# suit.net
KiCad netlist of a schematic drawn in EAGLE
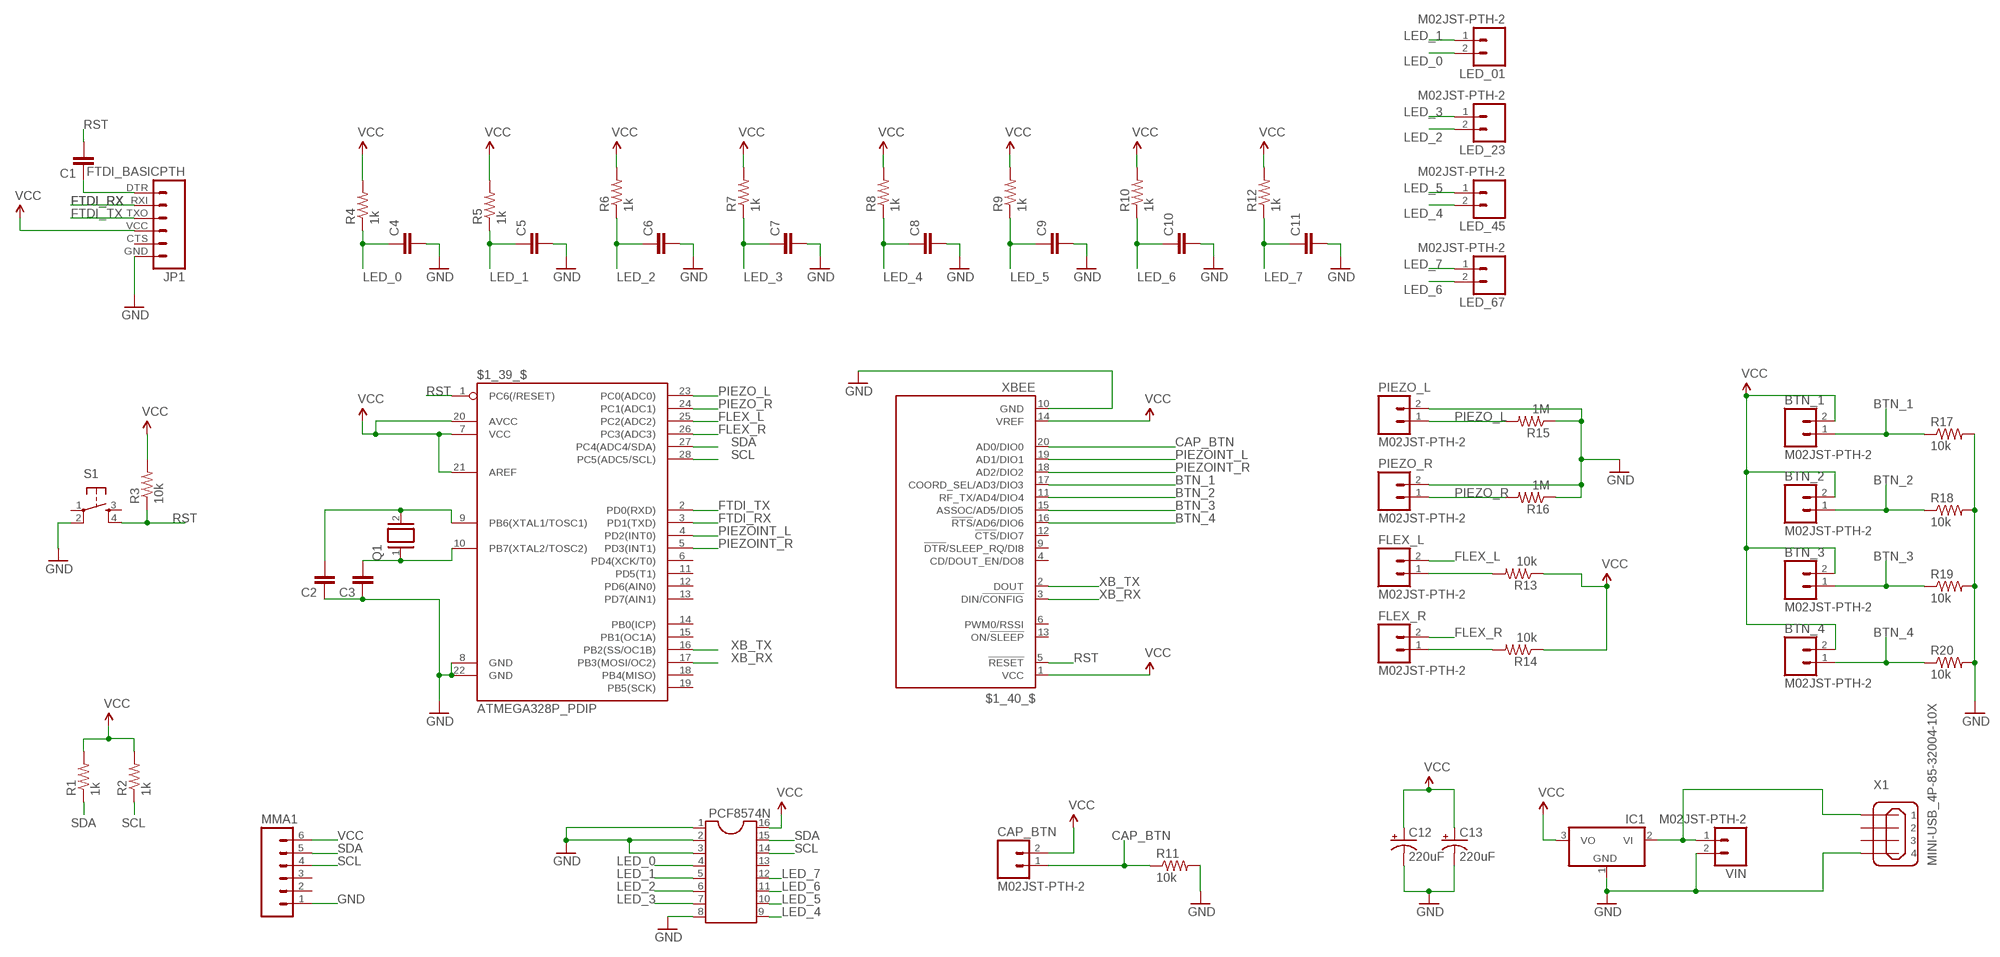
[diagram p0: schematic, sheet 1]

(export (version "E")
  (design (tool "Eeschema 10.0.6"))
  (components
    (comp (ref "$1_39_$")
      (value "ATMEGA328P_PDIP")
      (footprint "eagle-import:DIL28-3")
      (libsource (lib "eagle-import") (part "ATMEGA328P_PDIP"))
    )
    (comp (ref "$1_40_$")
      (value "XBEE")
      (footprint "eagle-import:XBEE")
      (fields (field (name "MPN") "XBP24-Z7UIT-004"))
      (libsource (lib "eagle-import") (part "XBEE"))
    )
    (comp (ref "BTN_1")
      (value "M02JST-PTH-2")
      (footprint "eagle-import:JST-2-PTH")
      (libsource (lib "eagle-import") (part "M02JST-PTH-2"))
    )
    (comp (ref "BTN_2")
      (value "M02JST-PTH-2")
      (footprint "eagle-import:JST-2-PTH")
      (libsource (lib "eagle-import") (part "M02JST-PTH-2"))
    )
    (comp (ref "BTN_3")
      (value "M02JST-PTH-2")
      (footprint "eagle-import:JST-2-PTH")
      (libsource (lib "eagle-import") (part "M02JST-PTH-2"))
    )
    (comp (ref "BTN_4")
      (value "M02JST-PTH-2")
      (footprint "eagle-import:JST-2-PTH")
      (libsource (lib "eagle-import") (part "M02JST-PTH-2"))
    )
    (comp (ref "C1")
      (value "CAPEZ")
      (footprint "eagle-import:CAP-PTH-SMALLEZ")
      (libsource (lib "eagle-import") (part "CAPEZ"))
    )
    (comp (ref "C2")
      (value "CAPEZ")
      (footprint "eagle-import:CAP-PTH-SMALLEZ")
      (libsource (lib "eagle-import") (part "CAPEZ"))
    )
    (comp (ref "C3")
      (value "CAPEZ")
      (footprint "eagle-import:CAP-PTH-SMALLEZ")
      (libsource (lib "eagle-import") (part "CAPEZ"))
    )
    (comp (ref "C4")
      (value "CAPEZ")
      (footprint "eagle-import:CAP-PTH-SMALLEZ")
      (libsource (lib "eagle-import") (part "CAPEZ"))
    )
    (comp (ref "C5")
      (value "CAPEZ")
      (footprint "eagle-import:CAP-PTH-SMALLEZ")
      (libsource (lib "eagle-import") (part "CAPEZ"))
    )
    (comp (ref "C6")
      (value "CAPEZ")
      (footprint "eagle-import:CAP-PTH-SMALLEZ")
      (libsource (lib "eagle-import") (part "CAPEZ"))
    )
    (comp (ref "C7")
      (value "CAPEZ")
      (footprint "eagle-import:CAP-PTH-SMALLEZ")
      (libsource (lib "eagle-import") (part "CAPEZ"))
    )
    (comp (ref "C8")
      (value "CAPEZ")
      (footprint "eagle-import:CAP-PTH-SMALLEZ")
      (libsource (lib "eagle-import") (part "CAPEZ"))
    )
    (comp (ref "C9")
      (value "CAPEZ")
      (footprint "eagle-import:CAP-PTH-SMALLEZ")
      (libsource (lib "eagle-import") (part "CAPEZ"))
    )
    (comp (ref "C10")
      (value "CAPEZ")
      (footprint "eagle-import:CAP-PTH-SMALLEZ")
      (libsource (lib "eagle-import") (part "CAPEZ"))
    )
    (comp (ref "C11")
      (value "CAPEZ")
      (footprint "eagle-import:CAP-PTH-SMALLEZ")
      (libsource (lib "eagle-import") (part "CAPEZ"))
    )
    (comp (ref "C12")
      (value "220uF")
      (footprint "eagle-import:B45181A")
      (libsource (lib "eagle-import") (part "CPOL-USB45181A"))
    )
    (comp (ref "C13")
      (value "220uF")
      (footprint "eagle-import:B45181A")
      (libsource (lib "eagle-import") (part "CPOL-USB45181A"))
    )
    (comp (ref "CAP_BTN")
      (value "M02JST-PTH-2")
      (footprint "eagle-import:JST-2-PTH")
      (libsource (lib "eagle-import") (part "M02JST-PTH-2"))
    )
    (comp (ref "FLEX_L")
      (value "M02JST-PTH-2")
      (footprint "eagle-import:JST-2-PTH")
      (libsource (lib "eagle-import") (part "M02JST-PTH-2"))
    )
    (comp (ref "FLEX_R")
      (value "M02JST-PTH-2")
      (footprint "eagle-import:JST-2-PTH")
      (libsource (lib "eagle-import") (part "M02JST-PTH-2"))
    )
    (comp (ref "IC1")
      (value "79L05Z")
      (footprint "eagle-import:TO92")
      (libsource (lib "eagle-import") (part "79ZL05"))
    )
    (comp (ref "JP1")
      (value "FTDI_BASICPTH")
      (footprint "eagle-import:FTDI_BASIC")
      (libsource (lib "eagle-import") (part "FTDI_BASICPTH"))
    )
    (comp (ref "LED_01")
      (value "M02JST-PTH-2")
      (footprint "eagle-import:JST-2-PTH")
      (libsource (lib "eagle-import") (part "M02JST-PTH-2"))
    )
    (comp (ref "LED_23")
      (value "M02JST-PTH-2")
      (footprint "eagle-import:JST-2-PTH")
      (libsource (lib "eagle-import") (part "M02JST-PTH-2"))
    )
    (comp (ref "LED_45")
      (value "M02JST-PTH-2")
      (footprint "eagle-import:JST-2-PTH")
      (libsource (lib "eagle-import") (part "M02JST-PTH-2"))
    )
    (comp (ref "LED_67")
      (value "M02JST-PTH-2")
      (footprint "eagle-import:JST-2-PTH")
      (libsource (lib "eagle-import") (part "M02JST-PTH-2"))
    )
    (comp (ref "MMA1")
      (value "M06FEMALE_LOCK")
      (footprint "eagle-import:1X06_FEMALE_LOCK.010")
      (libsource (lib "eagle-import") (part "M06FEMALE_LOCK"))
    )
    (comp (ref "PCF8574N")
      (value "DIL16S")
      (footprint "eagle-import:SOCKET-16")
      (libsource (lib "eagle-import") (part "DIL16S"))
    )
    (comp (ref "PIEZO_L")
      (value "M02JST-PTH-2")
      (footprint "eagle-import:JST-2-PTH")
      (libsource (lib "eagle-import") (part "M02JST-PTH-2"))
    )
    (comp (ref "PIEZO_R")
      (value "M02JST-PTH-2")
      (footprint "eagle-import:JST-2-PTH")
      (libsource (lib "eagle-import") (part "M02JST-PTH-2"))
    )
    (comp (ref "Q1")
      (value "XTAL/S")
      (footprint "eagle-import:QS")
      (libsource (lib "eagle-import") (part "XTAL/S"))
    )
    (comp (ref "R1")
      (value "1k")
      (footprint "eagle-import:0207_10")
      (libsource (lib "eagle-import") (part "R-US_0207/10"))
    )
    (comp (ref "R2")
      (value "1k")
      (footprint "eagle-import:0207_10")
      (libsource (lib "eagle-import") (part "R-US_0207/10"))
    )
    (comp (ref "R3")
      (value "10k")
      (footprint "eagle-import:0207_10")
      (libsource (lib "eagle-import") (part "R-US_0207/10"))
    )
    (comp (ref "R4")
      (value "1k")
      (footprint "eagle-import:0207_10")
      (libsource (lib "eagle-import") (part "R-US_0207/10"))
    )
    (comp (ref "R5")
      (value "1k")
      (footprint "eagle-import:0207_10")
      (libsource (lib "eagle-import") (part "R-US_0207/10"))
    )
    (comp (ref "R6")
      (value "1k")
      (footprint "eagle-import:0207_10")
      (libsource (lib "eagle-import") (part "R-US_0207/10"))
    )
    (comp (ref "R7")
      (value "1k")
      (footprint "eagle-import:0207_10")
      (libsource (lib "eagle-import") (part "R-US_0207/10"))
    )
    (comp (ref "R8")
      (value "1k")
      (footprint "eagle-import:0207_10")
      (libsource (lib "eagle-import") (part "R-US_0207/10"))
    )
    (comp (ref "R9")
      (value "1k")
      (footprint "eagle-import:0207_10")
      (libsource (lib "eagle-import") (part "R-US_0207/10"))
    )
    (comp (ref "R10")
      (value "1k")
      (footprint "eagle-import:0207_10")
      (libsource (lib "eagle-import") (part "R-US_0207/10"))
    )
    (comp (ref "R11")
      (value "10k")
      (footprint "eagle-import:0207_10")
      (libsource (lib "eagle-import") (part "R-US_0207/10"))
    )
    (comp (ref "R12")
      (value "1k")
      (footprint "eagle-import:0207_10")
      (libsource (lib "eagle-import") (part "R-US_0207/10"))
    )
    (comp (ref "R13")
      (value "10k")
      (footprint "eagle-import:0207_10")
      (libsource (lib "eagle-import") (part "R-US_0207/10"))
    )
    (comp (ref "R14")
      (value "10k")
      (footprint "eagle-import:0207_10")
      (libsource (lib "eagle-import") (part "R-US_0207/10"))
    )
    (comp (ref "R15")
      (value "1M")
      (footprint "eagle-import:0207_10")
      (libsource (lib "eagle-import") (part "R-US_0207/10"))
    )
    (comp (ref "R16")
      (value "1M")
      (footprint "eagle-import:0207_10")
      (libsource (lib "eagle-import") (part "R-US_0207/10"))
    )
    (comp (ref "R17")
      (value "10k")
      (footprint "eagle-import:0207_10")
      (libsource (lib "eagle-import") (part "R-US_0207/10"))
    )
    (comp (ref "R18")
      (value "10k")
      (footprint "eagle-import:0207_10")
      (libsource (lib "eagle-import") (part "R-US_0207/10"))
    )
    (comp (ref "R19")
      (value "10k")
      (footprint "eagle-import:0207_10")
      (libsource (lib "eagle-import") (part "R-US_0207/10"))
    )
    (comp (ref "R20")
      (value "10k")
      (footprint "eagle-import:0207_10")
      (libsource (lib "eagle-import") (part "R-US_0207/10"))
    )
    (comp (ref "S1")
      (value "TAC_SWITCHPTH")
      (footprint "eagle-import:TACTILE-PTH")
      (libsource (lib "eagle-import") (part "TAC_SWITCHPTH"))
    )
    (comp (ref "VIN")
      (value "M02JST-PTH-2")
      (footprint "eagle-import:JST-2-PTH")
      (libsource (lib "eagle-import") (part "M02JST-PTH-2"))
    )
    (comp (ref "X1")
      (value "MINI-USB_4P-85-32004-10X")
      (footprint "eagle-import:85-32004-10X")
      (libsource (lib "eagle-import") (part "MINI-USB_4P-85-32004-10X"))
    )
  )
  (nets
    (net (code "1") (name "/BTN_1") (class "Default")
      (node (ref "$1_40_$") (pin "17") (pinfunction "COORD_SEL/AD3/DIO3_17") (pintype "bidirectional"))
      (node (ref "BTN_1") (pin "1") (pinfunction "1_1") (pintype "passive"))
      (node (ref "R17") (pin "1") (pinfunction "1_1") (pintype "passive"))
    )
    (net (code "2") (name "/BTN_2") (class "Default")
      (node (ref "$1_40_$") (pin "11") (pinfunction "RF_TX/AD4/DIO4_11") (pintype "bidirectional"))
      (node (ref "BTN_2") (pin "1") (pinfunction "1_1") (pintype "passive"))
      (node (ref "R18") (pin "1") (pinfunction "1_1") (pintype "passive"))
    )
    (net (code "3") (name "/BTN_3") (class "Default")
      (node (ref "$1_40_$") (pin "15") (pinfunction "ASSOC/AD5/DIO5_15") (pintype "bidirectional"))
      (node (ref "BTN_3") (pin "1") (pinfunction "1_1") (pintype "passive"))
      (node (ref "R19") (pin "1") (pinfunction "1_1") (pintype "passive"))
    )
    (net (code "4") (name "/BTN_4") (class "Default")
      (node (ref "$1_40_$") (pin "16") (pinfunction "~{RTS}/AD6/DIO6_16") (pintype "bidirectional"))
      (node (ref "BTN_4") (pin "1") (pinfunction "1_1") (pintype "passive"))
      (node (ref "R20") (pin "1") (pinfunction "1_1") (pintype "passive"))
    )
    (net (code "5") (name "/CAP_BTN") (class "Default")
      (node (ref "$1_40_$") (pin "20") (pinfunction "AD0/DIO0_20") (pintype "bidirectional"))
      (node (ref "CAP_BTN") (pin "1") (pinfunction "1_1") (pintype "passive"))
      (node (ref "R11") (pin "1") (pinfunction "1_1") (pintype "passive"))
    )
    (net (code "6") (name "/FLEX_L") (class "Default")
      (node (ref "$1_39_$") (pin "25") (pinfunction "PC2(ADC2)_25") (pintype "bidirectional"))
      (node (ref "FLEX_L") (pin "2") (pinfunction "2_2") (pintype "passive"))
    )
    (net (code "7") (name "/FLEX_R") (class "Default")
      (node (ref "$1_39_$") (pin "26") (pinfunction "PC3(ADC3)_26") (pintype "bidirectional"))
      (node (ref "FLEX_R") (pin "2") (pinfunction "2_2") (pintype "passive"))
    )
    (net (code "8") (name "/FTDI_RX") (class "Default")
      (node (ref "$1_39_$") (pin "3") (pinfunction "PD1(TXD)_3") (pintype "bidirectional"))
      (node (ref "JP1") (pin "RXI") (pinfunction "2_RXI") (pintype "passive"))
    )
    (net (code "9") (name "/FTDI_TX") (class "Default")
      (node (ref "$1_39_$") (pin "2") (pinfunction "PD0(RXD)_2") (pintype "bidirectional"))
      (node (ref "JP1") (pin "TXO") (pinfunction "3_TXO") (pintype "passive"))
    )
    (net (code "10") (name "/LED_0") (class "Default")
      (node (ref "C4") (pin "1") (pinfunction "1_1") (pintype "passive"))
      (node (ref "LED_01") (pin "2") (pinfunction "2_2") (pintype "passive"))
      (node (ref "PCF8574N") (pin "4") (pinfunction "4_4") (pintype "passive"))
      (node (ref "R4") (pin "1") (pinfunction "1_1") (pintype "passive"))
    )
    (net (code "11") (name "/LED_1") (class "Default")
      (node (ref "C5") (pin "1") (pinfunction "1_1") (pintype "passive"))
      (node (ref "LED_01") (pin "1") (pinfunction "1_1") (pintype "passive"))
      (node (ref "PCF8574N") (pin "5") (pinfunction "5_5") (pintype "passive"))
      (node (ref "R5") (pin "1") (pinfunction "1_1") (pintype "passive"))
    )
    (net (code "12") (name "/LED_2") (class "Default")
      (node (ref "C6") (pin "1") (pinfunction "1_1") (pintype "passive"))
      (node (ref "LED_23") (pin "2") (pinfunction "2_2") (pintype "passive"))
      (node (ref "PCF8574N") (pin "6") (pinfunction "6_6") (pintype "passive"))
      (node (ref "R6") (pin "1") (pinfunction "1_1") (pintype "passive"))
    )
    (net (code "13") (name "/LED_3") (class "Default")
      (node (ref "C7") (pin "1") (pinfunction "1_1") (pintype "passive"))
      (node (ref "LED_23") (pin "1") (pinfunction "1_1") (pintype "passive"))
      (node (ref "PCF8574N") (pin "7") (pinfunction "7_7") (pintype "passive"))
      (node (ref "R7") (pin "1") (pinfunction "1_1") (pintype "passive"))
    )
    (net (code "14") (name "/LED_4") (class "Default")
      (node (ref "C8") (pin "1") (pinfunction "1_1") (pintype "passive"))
      (node (ref "LED_45") (pin "2") (pinfunction "2_2") (pintype "passive"))
      (node (ref "PCF8574N") (pin "9") (pinfunction "9_9") (pintype "passive"))
      (node (ref "R8") (pin "1") (pinfunction "1_1") (pintype "passive"))
    )
    (net (code "15") (name "/LED_5") (class "Default")
      (node (ref "C9") (pin "1") (pinfunction "1_1") (pintype "passive"))
      (node (ref "LED_45") (pin "1") (pinfunction "1_1") (pintype "passive"))
      (node (ref "PCF8574N") (pin "10") (pinfunction "10_10") (pintype "passive"))
      (node (ref "R9") (pin "1") (pinfunction "1_1") (pintype "passive"))
    )
    (net (code "16") (name "/LED_6") (class "Default")
      (node (ref "C10") (pin "1") (pinfunction "1_1") (pintype "passive"))
      (node (ref "LED_67") (pin "2") (pinfunction "2_2") (pintype "passive"))
      (node (ref "PCF8574N") (pin "11") (pinfunction "11_11") (pintype "passive"))
      (node (ref "R10") (pin "1") (pinfunction "1_1") (pintype "passive"))
    )
    (net (code "17") (name "/LED_7") (class "Default")
      (node (ref "C11") (pin "1") (pinfunction "1_1") (pintype "passive"))
      (node (ref "LED_67") (pin "1") (pinfunction "1_1") (pintype "passive"))
      (node (ref "PCF8574N") (pin "12") (pinfunction "12_12") (pintype "passive"))
      (node (ref "R12") (pin "1") (pinfunction "1_1") (pintype "passive"))
    )
    (net (code "18") (name "/PIEZOINT_L") (class "Default")
      (node (ref "$1_39_$") (pin "4") (pinfunction "PD2(INT0)_4") (pintype "bidirectional"))
      (node (ref "$1_40_$") (pin "19") (pinfunction "AD1/DIO1_19") (pintype "bidirectional"))
    )
    (net (code "19") (name "/PIEZOINT_R") (class "Default")
      (node (ref "$1_39_$") (pin "5") (pinfunction "PD3(INT1)_5") (pintype "bidirectional"))
      (node (ref "$1_40_$") (pin "18") (pinfunction "AD2/DIO2_18") (pintype "bidirectional"))
    )
    (net (code "20") (name "/PIEZO_L") (class "Default")
      (node (ref "$1_39_$") (pin "23") (pinfunction "PC0(ADC0)_23") (pintype "bidirectional"))
      (node (ref "PIEZO_L") (pin "1") (pinfunction "1_1") (pintype "passive"))
      (node (ref "R15") (pin "2") (pinfunction "2_2") (pintype "passive"))
    )
    (net (code "21") (name "/PIEZO_R") (class "Default")
      (node (ref "$1_39_$") (pin "24") (pinfunction "PC1(ADC1)_24") (pintype "bidirectional"))
      (node (ref "PIEZO_R") (pin "1") (pinfunction "1_1") (pintype "passive"))
      (node (ref "R16") (pin "2") (pinfunction "2_2") (pintype "passive"))
    )
    (net (code "22") (name "/RST") (class "Default")
      (node (ref "$1_39_$") (pin "1") (pinfunction "PC6(/RESET)_1") (pintype "bidirectional"))
      (node (ref "$1_40_$") (pin "5") (pinfunction "~{RESET}_5") (pintype "input"))
      (node (ref "C1") (pin "2") (pinfunction "2_2") (pintype "passive"))
      (node (ref "R3") (pin "1") (pinfunction "1_1") (pintype "passive"))
      (node (ref "S1") (pin "4") (pinfunction "4_4") (pintype "passive"))
    )
    (net (code "23") (name "/SCL") (class "Default")
      (node (ref "$1_39_$") (pin "28") (pinfunction "PC5(ADC5/SCL)_28") (pintype "bidirectional"))
      (node (ref "MMA1") (pin "4") (pinfunction "4_4") (pintype "passive"))
      (node (ref "PCF8574N") (pin "14") (pinfunction "14_14") (pintype "passive"))
      (node (ref "R2") (pin "1") (pinfunction "1_1") (pintype "passive"))
    )
    (net (code "24") (name "/SDA") (class "Default")
      (node (ref "$1_39_$") (pin "27") (pinfunction "PC4(ADC4/SDA)_27") (pintype "bidirectional"))
      (node (ref "MMA1") (pin "5") (pinfunction "5_5") (pintype "passive"))
      (node (ref "PCF8574N") (pin "15") (pinfunction "15_15") (pintype "passive"))
      (node (ref "R1") (pin "1") (pinfunction "1_1") (pintype "passive"))
    )
    (net (code "25") (name "/XB_RX") (class "Default")
      (node (ref "$1_39_$") (pin "17") (pinfunction "PB3(MOSI/OC2)_17") (pintype "bidirectional"))
      (node (ref "$1_40_$") (pin "3") (pinfunction "DIN/~{CONFIG}_3") (pintype "input"))
    )
    (net (code "26") (name "/XB_TX") (class "Default")
      (node (ref "$1_39_$") (pin "16") (pinfunction "PB2(SS/OC1B)_16") (pintype "bidirectional"))
      (node (ref "$1_40_$") (pin "2") (pinfunction "DOUT_2") (pintype "output"))
    )
    (net (code "27") (name "GND") (class "Default")
      (node (ref "$1_39_$") (pin "22") (pinfunction "GND_22") (pintype "bidirectional"))
      (node (ref "$1_39_$") (pin "8") (pinfunction "GND_8") (pintype "bidirectional"))
      (node (ref "$1_40_$") (pin "10") (pinfunction "GND_10") (pintype "power_in"))
      (node (ref "C10") (pin "2") (pinfunction "2_2") (pintype "passive"))
      (node (ref "C11") (pin "2") (pinfunction "2_2") (pintype "passive"))
      (node (ref "C12") (pin "-") (pinfunction "-_-") (pintype "passive"))
      (node (ref "C13") (pin "-") (pinfunction "-_-") (pintype "passive"))
      (node (ref "C2") (pin "1") (pinfunction "1_1") (pintype "passive"))
      (node (ref "C3") (pin "1") (pinfunction "1_1") (pintype "passive"))
      (node (ref "C4") (pin "2") (pinfunction "2_2") (pintype "passive"))
      (node (ref "C5") (pin "2") (pinfunction "2_2") (pintype "passive"))
      (node (ref "C6") (pin "2") (pinfunction "2_2") (pintype "passive"))
      (node (ref "C7") (pin "2") (pinfunction "2_2") (pintype "passive"))
      (node (ref "C8") (pin "2") (pinfunction "2_2") (pintype "passive"))
      (node (ref "C9") (pin "2") (pinfunction "2_2") (pintype "passive"))
      (node (ref "IC1") (pin "1") (pinfunction "GND_1") (pintype "passive"))
      (node (ref "JP1") (pin "GND") (pinfunction "6_GND") (pintype "passive"))
      (node (ref "MMA1") (pin "1") (pinfunction "1_1") (pintype "passive"))
      (node (ref "PCF8574N") (pin "1") (pinfunction "1_1") (pintype "passive"))
      (node (ref "PCF8574N") (pin "2") (pinfunction "2_2") (pintype "passive"))
      (node (ref "PCF8574N") (pin "3") (pinfunction "3_3") (pintype "passive"))
      (node (ref "PCF8574N") (pin "8") (pinfunction "8_8") (pintype "passive"))
      (node (ref "PIEZO_L") (pin "2") (pinfunction "2_2") (pintype "passive"))
      (node (ref "PIEZO_R") (pin "2") (pinfunction "2_2") (pintype "passive"))
      (node (ref "R11") (pin "2") (pinfunction "2_2") (pintype "passive"))
      (node (ref "R15") (pin "1") (pinfunction "1_1") (pintype "passive"))
      (node (ref "R16") (pin "1") (pinfunction "1_1") (pintype "passive"))
      (node (ref "R17") (pin "2") (pinfunction "2_2") (pintype "passive"))
      (node (ref "R18") (pin "2") (pinfunction "2_2") (pintype "passive"))
      (node (ref "R19") (pin "2") (pinfunction "2_2") (pintype "passive"))
      (node (ref "R20") (pin "2") (pinfunction "2_2") (pintype "passive"))
      (node (ref "S1") (pin "2") (pinfunction "2_2") (pintype "passive"))
      (node (ref "VIN") (pin "2") (pinfunction "2_2") (pintype "passive"))
      (node (ref "X1") (pin "4") (pinfunction "4_4") (pintype "passive"))
    )
    (net (code "28") (name "Net-($1_39_$-PB6(XTAL1{slash}TOSC1))") (class "Default")
      (node (ref "$1_39_$") (pin "9") (pinfunction "PB6(XTAL1/TOSC1)_9") (pintype "bidirectional"))
      (node (ref "C2") (pin "2") (pinfunction "2_2") (pintype "passive"))
      (node (ref "Q1") (pin "2") (pinfunction "2_2") (pintype "passive"))
    )
    (net (code "29") (name "Net-($1_39_$-PB7(XTAL2{slash}TOSC2))") (class "Default")
      (node (ref "$1_39_$") (pin "10") (pinfunction "PB7(XTAL2/TOSC2)_10") (pintype "bidirectional"))
      (node (ref "C3") (pin "2") (pinfunction "2_2") (pintype "passive"))
      (node (ref "Q1") (pin "1") (pinfunction "1_1") (pintype "passive"))
    )
    (net (code "30") (name "Net-(FLEX_L-Pad1)") (class "Default")
      (node (ref "FLEX_L") (pin "1") (pinfunction "1_1") (pintype "passive"))
      (node (ref "R13") (pin "2") (pinfunction "2_2") (pintype "passive"))
    )
    (net (code "31") (name "Net-(FLEX_R-Pad1)") (class "Default")
      (node (ref "FLEX_R") (pin "1") (pinfunction "1_1") (pintype "passive"))
      (node (ref "R14") (pin "2") (pinfunction "2_2") (pintype "passive"))
    )
    (net (code "32") (name "Net-(IC1-VI)") (class "Default")
      (node (ref "IC1") (pin "2") (pinfunction "VI_2") (pintype "input"))
      (node (ref "VIN") (pin "1") (pinfunction "1_1") (pintype "passive"))
      (node (ref "X1") (pin "1") (pinfunction "1_1") (pintype "passive"))
    )
    (net (code "33") (name "Net-(JP1-1)") (class "Default")
      (node (ref "C1") (pin "1") (pinfunction "1_1") (pintype "passive"))
      (node (ref "JP1") (pin "DTR") (pinfunction "1_DTR") (pintype "passive"))
    )
    (net (code "34") (name "VCC") (class "Default")
      (node (ref "$1_39_$") (pin "20") (pinfunction "AVCC_20") (pintype "bidirectional"))
      (node (ref "$1_39_$") (pin "21") (pinfunction "AREF_21") (pintype "bidirectional"))
      (node (ref "$1_39_$") (pin "7") (pinfunction "VCC_7") (pintype "bidirectional"))
      (node (ref "$1_40_$") (pin "1") (pinfunction "VCC_1") (pintype "power_in"))
      (node (ref "$1_40_$") (pin "14") (pinfunction "VREF_14") (pintype "input"))
      (node (ref "BTN_1") (pin "2") (pinfunction "2_2") (pintype "passive"))
      (node (ref "BTN_2") (pin "2") (pinfunction "2_2") (pintype "passive"))
      (node (ref "BTN_3") (pin "2") (pinfunction "2_2") (pintype "passive"))
      (node (ref "BTN_4") (pin "2") (pinfunction "2_2") (pintype "passive"))
      (node (ref "C12") (pin "+") (pinfunction "+_+") (pintype "passive"))
      (node (ref "C13") (pin "+") (pinfunction "+_+") (pintype "passive"))
      (node (ref "CAP_BTN") (pin "2") (pinfunction "2_2") (pintype "passive"))
      (node (ref "IC1") (pin "3") (pinfunction "VO_3") (pintype "passive"))
      (node (ref "JP1") (pin "VCC") (pinfunction "4_VCC") (pintype "passive"))
      (node (ref "MMA1") (pin "6") (pinfunction "6_6") (pintype "passive"))
      (node (ref "PCF8574N") (pin "16") (pinfunction "16_16") (pintype "passive"))
      (node (ref "R1") (pin "2") (pinfunction "2_2") (pintype "passive"))
      (node (ref "R10") (pin "2") (pinfunction "2_2") (pintype "passive"))
      (node (ref "R12") (pin "2") (pinfunction "2_2") (pintype "passive"))
      (node (ref "R13") (pin "1") (pinfunction "1_1") (pintype "passive"))
      (node (ref "R14") (pin "1") (pinfunction "1_1") (pintype "passive"))
      (node (ref "R2") (pin "2") (pinfunction "2_2") (pintype "passive"))
      (node (ref "R3") (pin "2") (pinfunction "2_2") (pintype "passive"))
      (node (ref "R4") (pin "2") (pinfunction "2_2") (pintype "passive"))
      (node (ref "R5") (pin "2") (pinfunction "2_2") (pintype "passive"))
      (node (ref "R6") (pin "2") (pinfunction "2_2") (pintype "passive"))
      (node (ref "R7") (pin "2") (pinfunction "2_2") (pintype "passive"))
      (node (ref "R8") (pin "2") (pinfunction "2_2") (pintype "passive"))
      (node (ref "R9") (pin "2") (pinfunction "2_2") (pintype "passive"))
    )
    (net (code "35") (name "unconnected-($1_39_$-PB0(ICP)-Pad14)") (class "Default")
      (node (ref "$1_39_$") (pin "14") (pinfunction "PB0(ICP)_14") (pintype "bidirectional"))
    )
    (net (code "36") (name "unconnected-($1_39_$-PB1(OC1A)-Pad15)") (class "Default")
      (node (ref "$1_39_$") (pin "15") (pinfunction "PB1(OC1A)_15") (pintype "bidirectional"))
    )
    (net (code "37") (name "unconnected-($1_39_$-PB4(MISO)-Pad18)") (class "Default")
      (node (ref "$1_39_$") (pin "18") (pinfunction "PB4(MISO)_18") (pintype "bidirectional"))
    )
    (net (code "38") (name "unconnected-($1_39_$-PB5(SCK)-Pad19)") (class "Default")
      (node (ref "$1_39_$") (pin "19") (pinfunction "PB5(SCK)_19") (pintype "bidirectional"))
    )
    (net (code "39") (name "unconnected-($1_39_$-PD4(XCK{slash}T0)-Pad6)") (class "Default")
      (node (ref "$1_39_$") (pin "6") (pinfunction "PD4(XCK/T0)_6") (pintype "bidirectional"))
    )
    (net (code "40") (name "unconnected-($1_39_$-PD5(T1)-Pad11)") (class "Default")
      (node (ref "$1_39_$") (pin "11") (pinfunction "PD5(T1)_11") (pintype "bidirectional"))
    )
    (net (code "41") (name "unconnected-($1_39_$-PD6(AIN0)-Pad12)") (class "Default")
      (node (ref "$1_39_$") (pin "12") (pinfunction "PD6(AIN0)_12") (pintype "bidirectional"))
    )
    (net (code "42") (name "unconnected-($1_39_$-PD7(AIN1)-Pad13)") (class "Default")
      (node (ref "$1_39_$") (pin "13") (pinfunction "PD7(AIN1)_13") (pintype "bidirectional"))
    )
    (net (code "43") (name "unconnected-($1_40_$-CD{slash}DOUT_EN{slash}DO8-Pad4)") (class "Default")
      (node (ref "$1_40_$") (pin "4") (pinfunction "CD/DOUT_EN/DO8_4") (pintype "output"))
    )
    (net (code "44") (name "unconnected-($1_40_$-ON{slash}~{SLEEP}-Pad13)") (class "Default")
      (node (ref "$1_40_$") (pin "13") (pinfunction "ON/~{SLEEP}_13") (pintype "output"))
    )
    (net (code "45") (name "unconnected-($1_40_$-PWM0{slash}RSSI-Pad6)") (class "Default")
      (node (ref "$1_40_$") (pin "6") (pinfunction "PWM0/RSSI_6") (pintype "output"))
    )
    (net (code "46") (name "unconnected-($1_40_$-~{CTS}{slash}DIO7-Pad12)") (class "Default")
      (node (ref "$1_40_$") (pin "12") (pinfunction "~{CTS}/DIO7_12") (pintype "bidirectional"))
    )
    (net (code "47") (name "unconnected-($1_40_$-~{DTR}{slash}SLEEP_RQ{slash}DI8-Pad9)") (class "Default")
      (node (ref "$1_40_$") (pin "9") (pinfunction "~{DTR}/SLEEP_RQ/DI8_9") (pintype "bidirectional"))
    )
    (net (code "48") (name "unconnected-(JP1-5-PadCTS)") (class "Default")
      (node (ref "JP1") (pin "CTS") (pinfunction "5_CTS") (pintype "passive"))
    )
    (net (code "49") (name "unconnected-(MMA1-Pad2)") (class "Default")
      (node (ref "MMA1") (pin "2") (pinfunction "2_2") (pintype "passive"))
    )
    (net (code "50") (name "unconnected-(MMA1-Pad3)") (class "Default")
      (node (ref "MMA1") (pin "3") (pinfunction "3_3") (pintype "passive"))
    )
    (net (code "51") (name "unconnected-(PCF8574N-Pad13)") (class "Default")
      (node (ref "PCF8574N") (pin "13") (pinfunction "13_13") (pintype "passive"))
    )
    (net (code "52") (name "unconnected-(S1-Pad1)") (class "Default")
      (node (ref "S1") (pin "1") (pinfunction "1_1") (pintype "passive"))
    )
    (net (code "53") (name "unconnected-(S1-Pad3)") (class "Default")
      (node (ref "S1") (pin "3") (pinfunction "3_3") (pintype "passive"))
    )
    (net (code "54") (name "unconnected-(X1-Pad2)") (class "Default")
      (node (ref "X1") (pin "2") (pinfunction "2_2") (pintype "passive"))
    )
    (net (code "55") (name "unconnected-(X1-Pad3)") (class "Default")
      (node (ref "X1") (pin "3") (pinfunction "3_3") (pintype "passive"))
    )
  )
)
